# tmtr_board_rev1_2.net
KiCad netlist of a schematic drawn in Altium Designer
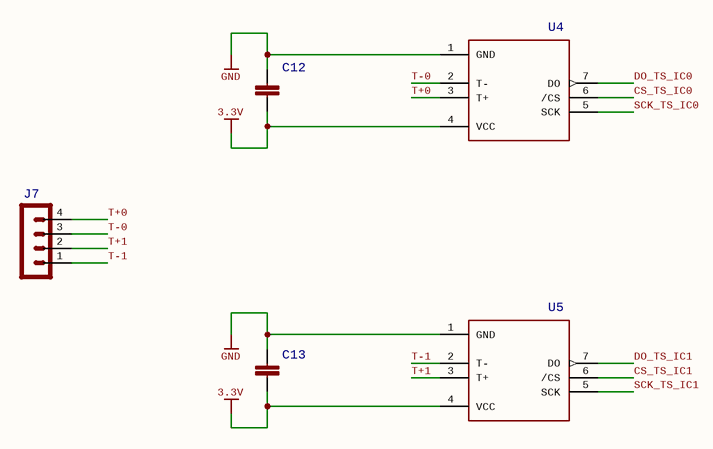
[diagram p0: tmtr_board_rev1_2.SchDoc]

(export (version "E")
  (design (tool "Eeschema 10.0.6"))
  (components
    (comp (ref "C12")
      (value "CAP0805")
      (footprint "0805")
      (description "<b>Capacitor</b>\nStandard 0603 ceramic capacitor, and 0.1\" leaded capacitor.")
      (libsource (lib "SparkFun1") (part "CAP0805"))
    )
    (comp (ref "C13")
      (value "CAP0805")
      (footprint "0805")
      (description "<b>Capacitor</b>\nStandard 0603 ceramic capacitor, and 0.1\" leaded capacitor.")
      (libsource (lib "SparkFun1") (part "CAP0805"))
    )
    (comp (ref "J7")
      (value "<b>PIN HEADER</b>")
      (footprint "MA04-1")
      (libsource (lib "con-lstb") (part "MA04-1"))
    )
    (comp (ref "U4") (value "MAX31855") (footprint "SO08") (libsource (lib "adafruit") (part "MAX6675")))
    (comp (ref "U5") (value "MAX31855") (footprint "SO08") (libsource (lib "adafruit") (part "MAX6675")))
  )
  (nets
    (net (code "1") (name "/CS_TS_IC0") (class "Default")
      (node (ref "U4") (pin "6") (pinfunction "/CS_6") (pintype "passive"))
    )
    (net (code "2") (name "/CS_TS_IC1") (class "Default")
      (node (ref "U5") (pin "6") (pinfunction "/CS_6") (pintype "passive"))
    )
    (net (code "3") (name "/DO_TS_IC0") (class "Default")
      (node (ref "U4") (pin "7") (pinfunction "DO_7") (pintype "output"))
    )
    (net (code "4") (name "/DO_TS_IC1") (class "Default")
      (node (ref "U5") (pin "7") (pinfunction "DO_7") (pintype "output"))
    )
    (net (code "5") (name "/SCK_TS_IC0") (class "Default")
      (node (ref "U4") (pin "5") (pinfunction "SCK_5") (pintype "passive"))
    )
    (net (code "6") (name "/SCK_TS_IC1") (class "Default")
      (node (ref "U5") (pin "5") (pinfunction "SCK_5") (pintype "passive"))
    )
    (net (code "7") (name "/T+0") (class "Default")
      (node (ref "J7") (pin "4") (pinfunction "4_4") (pintype "passive"))
      (node (ref "U4") (pin "3") (pinfunction "T+_3") (pintype "passive"))
    )
    (net (code "8") (name "/T+1") (class "Default")
      (node (ref "J7") (pin "2") (pinfunction "2_2") (pintype "passive"))
      (node (ref "U5") (pin "3") (pinfunction "T+_3") (pintype "passive"))
    )
    (net (code "9") (name "/T-0") (class "Default")
      (node (ref "J7") (pin "3") (pinfunction "3_3") (pintype "passive"))
      (node (ref "U4") (pin "2") (pinfunction "T-_2") (pintype "passive"))
    )
    (net (code "10") (name "/T-1") (class "Default")
      (node (ref "J7") (pin "1") (pinfunction "1_1") (pintype "passive"))
      (node (ref "U5") (pin "2") (pinfunction "T-_2") (pintype "passive"))
    )
    (net (code "11") (name "3.3V") (class "Default")
      (node (ref "C12") (pin "1") (pinfunction "1_1") (pintype "passive"))
      (node (ref "C13") (pin "1") (pinfunction "1_1") (pintype "passive"))
      (node (ref "U4") (pin "4") (pinfunction "VCC_4") (pintype "power_in"))
      (node (ref "U5") (pin "4") (pinfunction "VCC_4") (pintype "power_in"))
    )
    (net (code "12") (name "GND") (class "Default")
      (node (ref "C12") (pin "2") (pinfunction "2_2") (pintype "passive"))
      (node (ref "C13") (pin "2") (pinfunction "2_2") (pintype "passive"))
      (node (ref "U4") (pin "1") (pinfunction "GND_1") (pintype "power_in"))
      (node (ref "U5") (pin "1") (pinfunction "GND_1") (pintype "power_in"))
    )
  )
)
